# triac.net
KiCad netlist of a schematic drawn in EAGLE
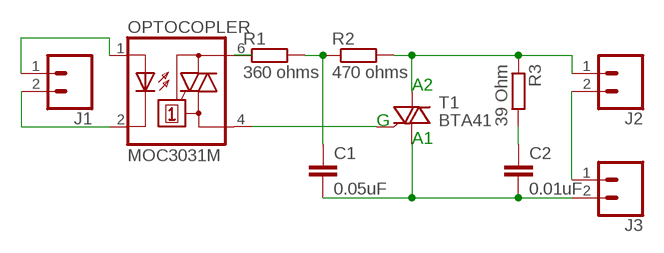
[diagram p0: schematic, sheet 1]

(export (version "E")
  (design (tool "Eeschema 10.0.6"))
  (components
    (comp (ref "C1")
      (value "0.05uF")
      (footprint "eagle-import:C7.5B3")
      (libsource (lib "eagle-import") (part "C7.5/3"))
    )
    (comp (ref "C2")
      (value "0.01uF")
      (footprint "eagle-import:C7.5B3")
      (libsource (lib "eagle-import") (part "C7.5/3"))
    )
    (comp (ref "J1")
      (value "CONN_02JST-PTH-2")
      (footprint "eagle-import:JST-2-PTH")
      (libsource (lib "eagle-import") (part "CONN_02JST-PTH-2"))
    )
    (comp (ref "J2")
      (value "CONN_02JST-PTH-2")
      (footprint "eagle-import:JST-2-PTH")
      (libsource (lib "eagle-import") (part "CONN_02JST-PTH-2"))
    )
    (comp (ref "J3")
      (value "CONN_02JST-PTH-2")
      (footprint "eagle-import:JST-2-PTH")
      (libsource (lib "eagle-import") (part "CONN_02JST-PTH-2"))
    )
    (comp (ref "OPTOCOPLER")
      (value "MOC3031M")
      (footprint "eagle-import:DIL06")
      (fields (field (name "MF") "FAIRCHILD SEMICONDUCTOR"))
      (libsource (lib "eagle-import") (part "MOC3031M"))
    )
    (comp (ref "R1")
      (value "360 ohms")
      (footprint "eagle-import:0204_5")
      (libsource (lib "eagle-import") (part "R-EU_0204/5"))
    )
    (comp (ref "R2")
      (value "470 ohms")
      (footprint "eagle-import:0204_5")
      (libsource (lib "eagle-import") (part "R-EU_0204/5"))
    )
    (comp (ref "R3")
      (value "39 Ohm")
      (footprint "eagle-import:0204_5")
      (libsource (lib "eagle-import") (part "R-EU_0204/5"))
    )
    (comp (ref "T1")
      (value "BTA41")
      (footprint "eagle-import:TO220BV")
      (libsource (lib "eagle-import") (part "BT138-V"))
    )
  )
  (nets
    (net (code "1") (name "Net-(C1-Pad1)") (class "Default")
      (node (ref "C1") (pin "1") (pinfunction "1_1") (pintype "passive"))
      (node (ref "R1") (pin "2") (pinfunction "2_2") (pintype "passive"))
      (node (ref "R2") (pin "1") (pinfunction "1_1") (pintype "passive"))
    )
    (net (code "2") (name "Net-(C2-Pad1)") (class "Default")
      (node (ref "C2") (pin "1") (pinfunction "1_1") (pintype "passive"))
      (node (ref "R3") (pin "2") (pinfunction "2_2") (pintype "passive"))
    )
    (net (code "3") (name "Net-(J2-Pad2)") (class "Default")
      (node (ref "J2") (pin "2") (pinfunction "2_2") (pintype "passive"))
      (node (ref "J3") (pin "1") (pinfunction "1_1") (pintype "passive"))
    )
    (net (code "4") (name "Net-(OPTOCOPLER-A)") (class "Default")
      (node (ref "J1") (pin "1") (pinfunction "1_1") (pintype "passive"))
      (node (ref "OPTOCOPLER") (pin "1") (pinfunction "A_1") (pintype "passive"))
    )
    (net (code "5") (name "Net-(OPTOCOPLER-A1)") (class "Default")
      (node (ref "OPTOCOPLER") (pin "4") (pinfunction "A1_4") (pintype "passive"))
      (node (ref "T1") (pin "G") (pinfunction "G_G") (pintype "passive"))
    )
    (net (code "6") (name "Net-(OPTOCOPLER-A2)") (class "Default")
      (node (ref "OPTOCOPLER") (pin "6") (pinfunction "A2_6") (pintype "passive"))
      (node (ref "R1") (pin "1") (pinfunction "1_1") (pintype "passive"))
    )
    (net (code "7") (name "Net-(OPTOCOPLER-C)") (class "Default")
      (node (ref "J1") (pin "2") (pinfunction "2_2") (pintype "passive"))
      (node (ref "OPTOCOPLER") (pin "2") (pinfunction "C_2") (pintype "passive"))
    )
    (net (code "8") (name "Net-(T1-A1)") (class "Default")
      (node (ref "C1") (pin "2") (pinfunction "2_2") (pintype "passive"))
      (node (ref "C2") (pin "2") (pinfunction "2_2") (pintype "passive"))
      (node (ref "J3") (pin "2") (pinfunction "2_2") (pintype "passive"))
      (node (ref "T1") (pin "T1") (pinfunction "A1_T1") (pintype "passive"))
    )
    (net (code "9") (name "Net-(T1-A2)") (class "Default")
      (node (ref "J2") (pin "1") (pinfunction "1_1") (pintype "passive"))
      (node (ref "R2") (pin "2") (pinfunction "2_2") (pintype "passive"))
      (node (ref "R3") (pin "1") (pinfunction "1_1") (pintype "passive"))
      (node (ref "T1") (pin "T2") (pinfunction "A2_T2") (pintype "passive"))
    )
  )
)
